# state_control.net
KiCad netlist of a schematic drawn in EAGLE
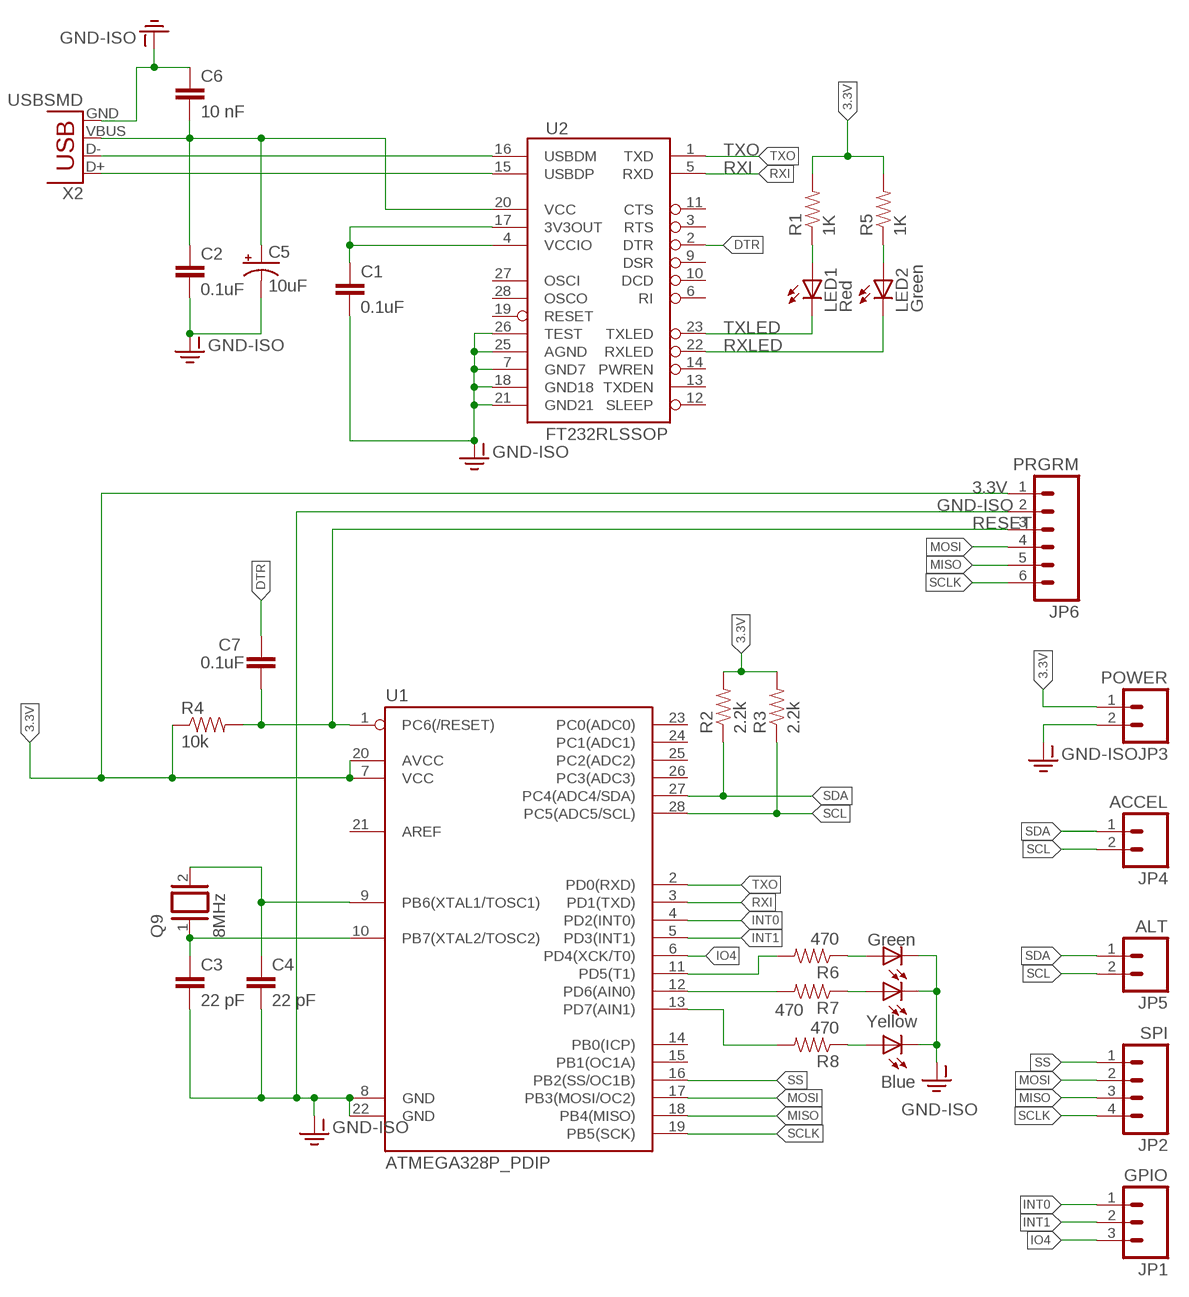
[diagram p0: schematic, sheet 1]

(export (version "E")
  (design (tool "Eeschema 10.0.6"))
  (components
    (comp (ref "C1")
      (value "0.1uF")
      (footprint "eagle-import:CAP-PTH-SMALL")
      (libsource (lib "eagle-import") (part "CAPPTH"))
    )
    (comp (ref "C2")
      (value "0.1uF")
      (footprint "eagle-import:CAP-PTH-SMALL")
      (libsource (lib "eagle-import") (part "CAPPTH"))
    )
    (comp (ref "C3")
      (value "22 pF")
      (footprint "eagle-import:CAP-PTH-SMALL")
      (libsource (lib "eagle-import") (part "CAPPTH"))
    )
    (comp (ref "C4")
      (value "22 pF")
      (footprint "eagle-import:CAP-PTH-SMALL")
      (libsource (lib "eagle-import") (part "CAPPTH"))
    )
    (comp (ref "C5")
      (value "10uF")
      (footprint "eagle-import:CPOL-RADIAL-10UF-25V")
      (libsource (lib "eagle-import") (part "CAP_POLPTH2"))
    )
    (comp (ref "C6")
      (value "10 nF")
      (footprint "eagle-import:CAP-PTH-SMALL")
      (libsource (lib "eagle-import") (part "CAPPTH"))
    )
    (comp (ref "C7")
      (value "0.1uF")
      (footprint "eagle-import:CAP-PTH-SMALL")
      (libsource (lib "eagle-import") (part "CAPPTH"))
    )
    (comp (ref "JP1")
      (value "GPIO")
      (footprint "eagle-import:1X03")
      (libsource (lib "eagle-import") (part "M03PTH"))
    )
    (comp (ref "JP2")
      (value "SPI")
      (footprint "eagle-import:1X04")
      (libsource (lib "eagle-import") (part "M04PTH"))
    )
    (comp (ref "JP3")
      (value "POWER")
      (footprint "eagle-import:1X02")
      (libsource (lib "eagle-import") (part "M02PTH"))
    )
    (comp (ref "JP4")
      (value "ACCEL")
      (footprint "eagle-import:1X02")
      (libsource (lib "eagle-import") (part "M02PTH"))
    )
    (comp (ref "JP5")
      (value "ALT")
      (footprint "eagle-import:1X02")
      (libsource (lib "eagle-import") (part "M02PTH"))
    )
    (comp (ref "JP6")
      (value "PRGRM")
      (footprint "eagle-import:1X06")
      (libsource (lib "eagle-import") (part "M06SILK_FEMALE_PTH"))
    )
    (comp (ref "LED1")
      (value "Red")
      (footprint "eagle-import:LED5MM")
      (libsource (lib "eagle-import") (part "LED5MM"))
    )
    (comp (ref "LED2")
      (value "Green")
      (footprint "eagle-import:LED5MM")
      (libsource (lib "eagle-import") (part "LED5MM"))
    )
    (comp (ref "LED3")
      (value "Green")
      (footprint "eagle-import:LED5MM")
      (libsource (lib "eagle-import") (part "LED5MM"))
    )
    (comp (ref "LED4")
      (value "Yellow")
      (footprint "eagle-import:LED5MM")
      (libsource (lib "eagle-import") (part "LED5MM"))
    )
    (comp (ref "LED5")
      (value "Blue")
      (footprint "eagle-import:LED5MM")
      (libsource (lib "eagle-import") (part "LED5MM"))
    )
    (comp (ref "Q9")
      (value "8MHz")
      (footprint "eagle-import:QS")
      (libsource (lib "eagle-import") (part "XTAL/S"))
    )
    (comp (ref "R1")
      (value "1K")
      (footprint "eagle-import:1206")
      (libsource (lib "eagle-import") (part "SparkFun-Resistors_RESISTOR1206"))
    )
    (comp (ref "R2")
      (value "2.2k")
      (footprint "eagle-import:1206")
      (libsource (lib "eagle-import") (part "RESISTOR1206"))
    )
    (comp (ref "R3")
      (value "2.2k")
      (footprint "eagle-import:1206")
      (libsource (lib "eagle-import") (part "RESISTOR1206"))
    )
    (comp (ref "R4")
      (value "10k")
      (footprint "eagle-import:1206")
      (libsource (lib "eagle-import") (part "RESISTOR1206"))
    )
    (comp (ref "R5")
      (value "1K")
      (footprint "eagle-import:1206")
      (libsource (lib "eagle-import") (part "SparkFun-Resistors_RESISTOR1206"))
    )
    (comp (ref "R6")
      (value "470")
      (footprint "eagle-import:1206")
      (libsource (lib "eagle-import") (part "RESISTOR1206"))
    )
    (comp (ref "R7")
      (value "470")
      (footprint "eagle-import:1206")
      (libsource (lib "eagle-import") (part "RESISTOR1206"))
    )
    (comp (ref "R8")
      (value "470")
      (footprint "eagle-import:1206")
      (libsource (lib "eagle-import") (part "RESISTOR1206"))
    )
    (comp (ref "U1")
      (value "ATMEGA328P_PDIP")
      (footprint "eagle-import:DIL28-3")
      (libsource (lib "eagle-import") (part "ATMEGA328P_PDIP"))
    )
    (comp (ref "U2")
      (value "FT232RLSSOP")
      (footprint "eagle-import:SSOP28DB")
      (libsource (lib "eagle-import") (part "FT232RLSSOP"))
    )
    (comp (ref "X2")
      (value "USBSMD")
      (footprint "eagle-import:USB-MINIB")
      (libsource (lib "eagle-import") (part "USBSMD"))
    )
  )
  (nets
    (net (code "1") (name "/RESET") (class "Default")
      (node (ref "C7") (pin "2") (pinfunction "2_2") (pintype "passive"))
      (node (ref "JP6") (pin "3") (pinfunction "3_3") (pintype "passive"))
      (node (ref "R4") (pin "2") (pinfunction "2_2") (pintype "passive"))
      (node (ref "U1") (pin "1") (pinfunction "PC6(/RESET)_1") (pintype "bidirectional"))
    )
    (net (code "2") (name "/RXLED") (class "Default")
      (node (ref "LED2") (pin "K") (pinfunction "C_K") (pintype "passive"))
      (node (ref "U2") (pin "22") (pinfunction "RXLED_22") (pintype "input"))
    )
    (net (code "3") (name "/TXLED") (class "Default")
      (node (ref "LED1") (pin "K") (pinfunction "C_K") (pintype "passive"))
      (node (ref "U2") (pin "23") (pinfunction "TXLED_23") (pintype "input"))
    )
    (net (code "4") (name "3.3V") (class "Default")
      (node (ref "JP3") (pin "1") (pinfunction "1_1") (pintype "passive"))
      (node (ref "JP6") (pin "1") (pinfunction "1_1") (pintype "passive"))
      (node (ref "R1") (pin "2") (pinfunction "2_2") (pintype "passive"))
      (node (ref "R2") (pin "2") (pinfunction "2_2") (pintype "passive"))
      (node (ref "R3") (pin "2") (pinfunction "2_2") (pintype "passive"))
      (node (ref "R4") (pin "1") (pinfunction "1_1") (pintype "passive"))
      (node (ref "R5") (pin "2") (pinfunction "2_2") (pintype "passive"))
      (node (ref "U1") (pin "20") (pinfunction "AVCC_20") (pintype "bidirectional"))
      (node (ref "U1") (pin "7") (pinfunction "VCC_7") (pintype "bidirectional"))
    )
    (net (code "5") (name "DTR") (class "Default")
      (node (ref "C7") (pin "1") (pinfunction "1_1") (pintype "passive"))
      (node (ref "U2") (pin "2") (pinfunction "DTR_2") (pintype "output"))
    )
    (net (code "6") (name "GND-ISO") (class "Default")
      (node (ref "C1") (pin "2") (pinfunction "2_2") (pintype "passive"))
      (node (ref "C2") (pin "2") (pinfunction "2_2") (pintype "passive"))
      (node (ref "C3") (pin "2") (pinfunction "2_2") (pintype "passive"))
      (node (ref "C4") (pin "2") (pinfunction "2_2") (pintype "passive"))
      (node (ref "C5") (pin "2") (pinfunction "-_2") (pintype "passive"))
      (node (ref "C6") (pin "1") (pinfunction "1_1") (pintype "passive"))
      (node (ref "JP3") (pin "2") (pinfunction "2_2") (pintype "passive"))
      (node (ref "JP6") (pin "2") (pinfunction "2_2") (pintype "passive"))
      (node (ref "LED3") (pin "K") (pinfunction "C_K") (pintype "passive"))
      (node (ref "LED4") (pin "K") (pinfunction "C_K") (pintype "passive"))
      (node (ref "LED5") (pin "K") (pinfunction "C_K") (pintype "passive"))
      (node (ref "U1") (pin "22") (pinfunction "GND_22") (pintype "bidirectional"))
      (node (ref "U1") (pin "8") (pinfunction "GND_8") (pintype "bidirectional"))
      (node (ref "U2") (pin "18") (pinfunction "GND18_18") (pintype "power_in"))
      (node (ref "U2") (pin "21") (pinfunction "GND21_21") (pintype "power_in"))
      (node (ref "U2") (pin "25") (pinfunction "AGND_25") (pintype "power_in"))
      (node (ref "U2") (pin "26") (pinfunction "TEST_26") (pintype "input"))
      (node (ref "U2") (pin "7") (pinfunction "GND7_7") (pintype "power_in"))
      (node (ref "X2") (pin "GND") (pinfunction "GND_GND") (pintype "bidirectional"))
    )
    (net (code "7") (name "INT0") (class "Default")
      (node (ref "JP1") (pin "1") (pinfunction "1_1") (pintype "passive"))
      (node (ref "U1") (pin "4") (pinfunction "PD2(INT0)_4") (pintype "bidirectional"))
    )
    (net (code "8") (name "INT1") (class "Default")
      (node (ref "JP1") (pin "2") (pinfunction "2_2") (pintype "passive"))
      (node (ref "U1") (pin "5") (pinfunction "PD3(INT1)_5") (pintype "bidirectional"))
    )
    (net (code "9") (name "IO4") (class "Default")
      (node (ref "JP1") (pin "3") (pinfunction "3_3") (pintype "passive"))
      (node (ref "U1") (pin "6") (pinfunction "PD4(XCK/T0)_6") (pintype "bidirectional"))
    )
    (net (code "10") (name "MISO") (class "Default")
      (node (ref "JP2") (pin "3") (pinfunction "3_3") (pintype "passive"))
      (node (ref "JP6") (pin "5") (pinfunction "5_5") (pintype "passive"))
      (node (ref "U1") (pin "18") (pinfunction "PB4(MISO)_18") (pintype "bidirectional"))
    )
    (net (code "11") (name "MOSI") (class "Default")
      (node (ref "JP2") (pin "2") (pinfunction "2_2") (pintype "passive"))
      (node (ref "JP6") (pin "4") (pinfunction "4_4") (pintype "passive"))
      (node (ref "U1") (pin "17") (pinfunction "PB3(MOSI/OC2)_17") (pintype "bidirectional"))
    )
    (net (code "12") (name "Net-(C5-+)") (class "Default")
      (node (ref "C2") (pin "1") (pinfunction "1_1") (pintype "passive"))
      (node (ref "C5") (pin "1") (pinfunction "+_1") (pintype "passive"))
      (node (ref "C6") (pin "2") (pinfunction "2_2") (pintype "passive"))
      (node (ref "U2") (pin "20") (pinfunction "VCC_20") (pintype "power_in"))
      (node (ref "X2") (pin "VBUS") (pinfunction "VBUS_VBUS") (pintype "bidirectional"))
    )
    (net (code "13") (name "Net-(LED1-PadA)") (class "Default")
      (node (ref "LED1") (pin "A") (pinfunction "A_A") (pintype "passive"))
      (node (ref "R1") (pin "1") (pinfunction "1_1") (pintype "passive"))
    )
    (net (code "14") (name "Net-(LED2-PadA)") (class "Default")
      (node (ref "LED2") (pin "A") (pinfunction "A_A") (pintype "passive"))
      (node (ref "R5") (pin "1") (pinfunction "1_1") (pintype "passive"))
    )
    (net (code "15") (name "Net-(LED3-PadA)") (class "Default")
      (node (ref "LED3") (pin "A") (pinfunction "A_A") (pintype "passive"))
      (node (ref "R6") (pin "1") (pinfunction "1_1") (pintype "passive"))
    )
    (net (code "16") (name "Net-(LED4-PadA)") (class "Default")
      (node (ref "LED4") (pin "A") (pinfunction "A_A") (pintype "passive"))
      (node (ref "R7") (pin "1") (pinfunction "1_1") (pintype "passive"))
    )
    (net (code "17") (name "Net-(LED5-PadA)") (class "Default")
      (node (ref "LED5") (pin "A") (pinfunction "A_A") (pintype "passive"))
      (node (ref "R8") (pin "1") (pinfunction "1_1") (pintype "passive"))
    )
    (net (code "18") (name "Net-(U1-PB6(XTAL1{slash}TOSC1))") (class "Default")
      (node (ref "C4") (pin "1") (pinfunction "1_1") (pintype "passive"))
      (node (ref "Q9") (pin "2") (pinfunction "2_2") (pintype "passive"))
      (node (ref "U1") (pin "9") (pinfunction "PB6(XTAL1/TOSC1)_9") (pintype "bidirectional"))
    )
    (net (code "19") (name "Net-(U1-PB7(XTAL2{slash}TOSC2))") (class "Default")
      (node (ref "C3") (pin "1") (pinfunction "1_1") (pintype "passive"))
      (node (ref "Q9") (pin "1") (pinfunction "1_1") (pintype "passive"))
      (node (ref "U1") (pin "10") (pinfunction "PB7(XTAL2/TOSC2)_10") (pintype "bidirectional"))
    )
    (net (code "20") (name "Net-(U1-PD5(T1))") (class "Default")
      (node (ref "R6") (pin "2") (pinfunction "2_2") (pintype "passive"))
      (node (ref "U1") (pin "11") (pinfunction "PD5(T1)_11") (pintype "bidirectional"))
    )
    (net (code "21") (name "Net-(U1-PD6(AIN0))") (class "Default")
      (node (ref "R7") (pin "2") (pinfunction "2_2") (pintype "passive"))
      (node (ref "U1") (pin "12") (pinfunction "PD6(AIN0)_12") (pintype "bidirectional"))
    )
    (net (code "22") (name "Net-(U1-PD7(AIN1))") (class "Default")
      (node (ref "R8") (pin "2") (pinfunction "2_2") (pintype "passive"))
      (node (ref "U1") (pin "13") (pinfunction "PD7(AIN1)_13") (pintype "bidirectional"))
    )
    (net (code "23") (name "Net-(U2-3V3OUT)") (class "Default")
      (node (ref "C1") (pin "1") (pinfunction "1_1") (pintype "passive"))
      (node (ref "U2") (pin "17") (pinfunction "3V3OUT_17") (pintype "output"))
      (node (ref "U2") (pin "4") (pinfunction "VCCIO_4") (pintype "power_in"))
    )
    (net (code "24") (name "Net-(U2-USBDM)") (class "Default")
      (node (ref "U2") (pin "16") (pinfunction "USBDM_16") (pintype "bidirectional"))
      (node (ref "X2") (pin "D-") (pinfunction "D-_D-") (pintype "bidirectional"))
    )
    (net (code "25") (name "Net-(U2-USBDP)") (class "Default")
      (node (ref "U2") (pin "15") (pinfunction "USBDP_15") (pintype "bidirectional"))
      (node (ref "X2") (pin "D+") (pinfunction "D+_D+") (pintype "bidirectional"))
    )
    (net (code "26") (name "RXI") (class "Default")
      (node (ref "U1") (pin "3") (pinfunction "PD1(TXD)_3") (pintype "bidirectional"))
      (node (ref "U2") (pin "5") (pinfunction "RXD_5") (pintype "input"))
    )
    (net (code "27") (name "SCL") (class "Default")
      (node (ref "JP4") (pin "2") (pinfunction "2_2") (pintype "passive"))
      (node (ref "JP5") (pin "2") (pinfunction "2_2") (pintype "passive"))
      (node (ref "R3") (pin "1") (pinfunction "1_1") (pintype "passive"))
      (node (ref "U1") (pin "28") (pinfunction "PC5(ADC5/SCL)_28") (pintype "bidirectional"))
    )
    (net (code "28") (name "SCLK") (class "Default")
      (node (ref "JP2") (pin "4") (pinfunction "4_4") (pintype "passive"))
      (node (ref "JP6") (pin "6") (pinfunction "6_6") (pintype "passive"))
      (node (ref "U1") (pin "19") (pinfunction "PB5(SCK)_19") (pintype "bidirectional"))
    )
    (net (code "29") (name "SDA") (class "Default")
      (node (ref "JP4") (pin "1") (pinfunction "1_1") (pintype "passive"))
      (node (ref "JP5") (pin "1") (pinfunction "1_1") (pintype "passive"))
      (node (ref "R2") (pin "1") (pinfunction "1_1") (pintype "passive"))
      (node (ref "U1") (pin "27") (pinfunction "PC4(ADC4/SDA)_27") (pintype "bidirectional"))
    )
    (net (code "30") (name "SS") (class "Default")
      (node (ref "JP2") (pin "1") (pinfunction "1_1") (pintype "passive"))
      (node (ref "U1") (pin "16") (pinfunction "PB2(SS/OC1B)_16") (pintype "bidirectional"))
    )
    (net (code "31") (name "TXO") (class "Default")
      (node (ref "U1") (pin "2") (pinfunction "PD0(RXD)_2") (pintype "bidirectional"))
      (node (ref "U2") (pin "1") (pinfunction "TXD_1") (pintype "output"))
    )
    (net (code "32") (name "unconnected-(U1-AREF-Pad21)") (class "Default")
      (node (ref "U1") (pin "21") (pinfunction "AREF_21") (pintype "bidirectional"))
    )
    (net (code "33") (name "unconnected-(U1-PB0(ICP)-Pad14)") (class "Default")
      (node (ref "U1") (pin "14") (pinfunction "PB0(ICP)_14") (pintype "bidirectional"))
    )
    (net (code "34") (name "unconnected-(U1-PB1(OC1A)-Pad15)") (class "Default")
      (node (ref "U1") (pin "15") (pinfunction "PB1(OC1A)_15") (pintype "bidirectional"))
    )
    (net (code "35") (name "unconnected-(U1-PC0(ADC0)-Pad23)") (class "Default")
      (node (ref "U1") (pin "23") (pinfunction "PC0(ADC0)_23") (pintype "bidirectional"))
    )
    (net (code "36") (name "unconnected-(U1-PC1(ADC1)-Pad24)") (class "Default")
      (node (ref "U1") (pin "24") (pinfunction "PC1(ADC1)_24") (pintype "bidirectional"))
    )
    (net (code "37") (name "unconnected-(U1-PC2(ADC2)-Pad25)") (class "Default")
      (node (ref "U1") (pin "25") (pinfunction "PC2(ADC2)_25") (pintype "bidirectional"))
    )
    (net (code "38") (name "unconnected-(U1-PC3(ADC3)-Pad26)") (class "Default")
      (node (ref "U1") (pin "26") (pinfunction "PC3(ADC3)_26") (pintype "bidirectional"))
    )
    (net (code "39") (name "unconnected-(U2-CTS-Pad11)") (class "Default")
      (node (ref "U2") (pin "11") (pinfunction "CTS_11") (pintype "input"))
    )
    (net (code "40") (name "unconnected-(U2-DCD-Pad10)") (class "Default")
      (node (ref "U2") (pin "10") (pinfunction "DCD_10") (pintype "input"))
    )
    (net (code "41") (name "unconnected-(U2-DSR-Pad9)") (class "Default")
      (node (ref "U2") (pin "9") (pinfunction "DSR_9") (pintype "input"))
    )
    (net (code "42") (name "unconnected-(U2-OSCI-Pad27)") (class "Default")
      (node (ref "U2") (pin "27") (pinfunction "OSCI_27") (pintype "input"))
    )
    (net (code "43") (name "unconnected-(U2-OSCO-Pad28)") (class "Default")
      (node (ref "U2") (pin "28") (pinfunction "OSCO_28") (pintype "output"))
    )
    (net (code "44") (name "unconnected-(U2-PWREN-Pad14)") (class "Default")
      (node (ref "U2") (pin "14") (pinfunction "PWREN_14") (pintype "input"))
    )
    (net (code "45") (name "unconnected-(U2-RESET-Pad19)") (class "Default")
      (node (ref "U2") (pin "19") (pinfunction "RESET_19") (pintype "input"))
    )
    (net (code "46") (name "unconnected-(U2-RI-Pad6)") (class "Default")
      (node (ref "U2") (pin "6") (pinfunction "RI_6") (pintype "input"))
    )
    (net (code "47") (name "unconnected-(U2-RTS-Pad3)") (class "Default")
      (node (ref "U2") (pin "3") (pinfunction "RTS_3") (pintype "output"))
    )
    (net (code "48") (name "unconnected-(U2-SLEEP-Pad12)") (class "Default")
      (node (ref "U2") (pin "12") (pinfunction "SLEEP_12") (pintype "input"))
    )
    (net (code "49") (name "unconnected-(U2-TXDEN-Pad13)") (class "Default")
      (node (ref "U2") (pin "13") (pinfunction "TXDEN_13") (pintype "input"))
    )
  )
)
